# CAN.net
KiCad netlist of a schematic drawn in Altium Designer
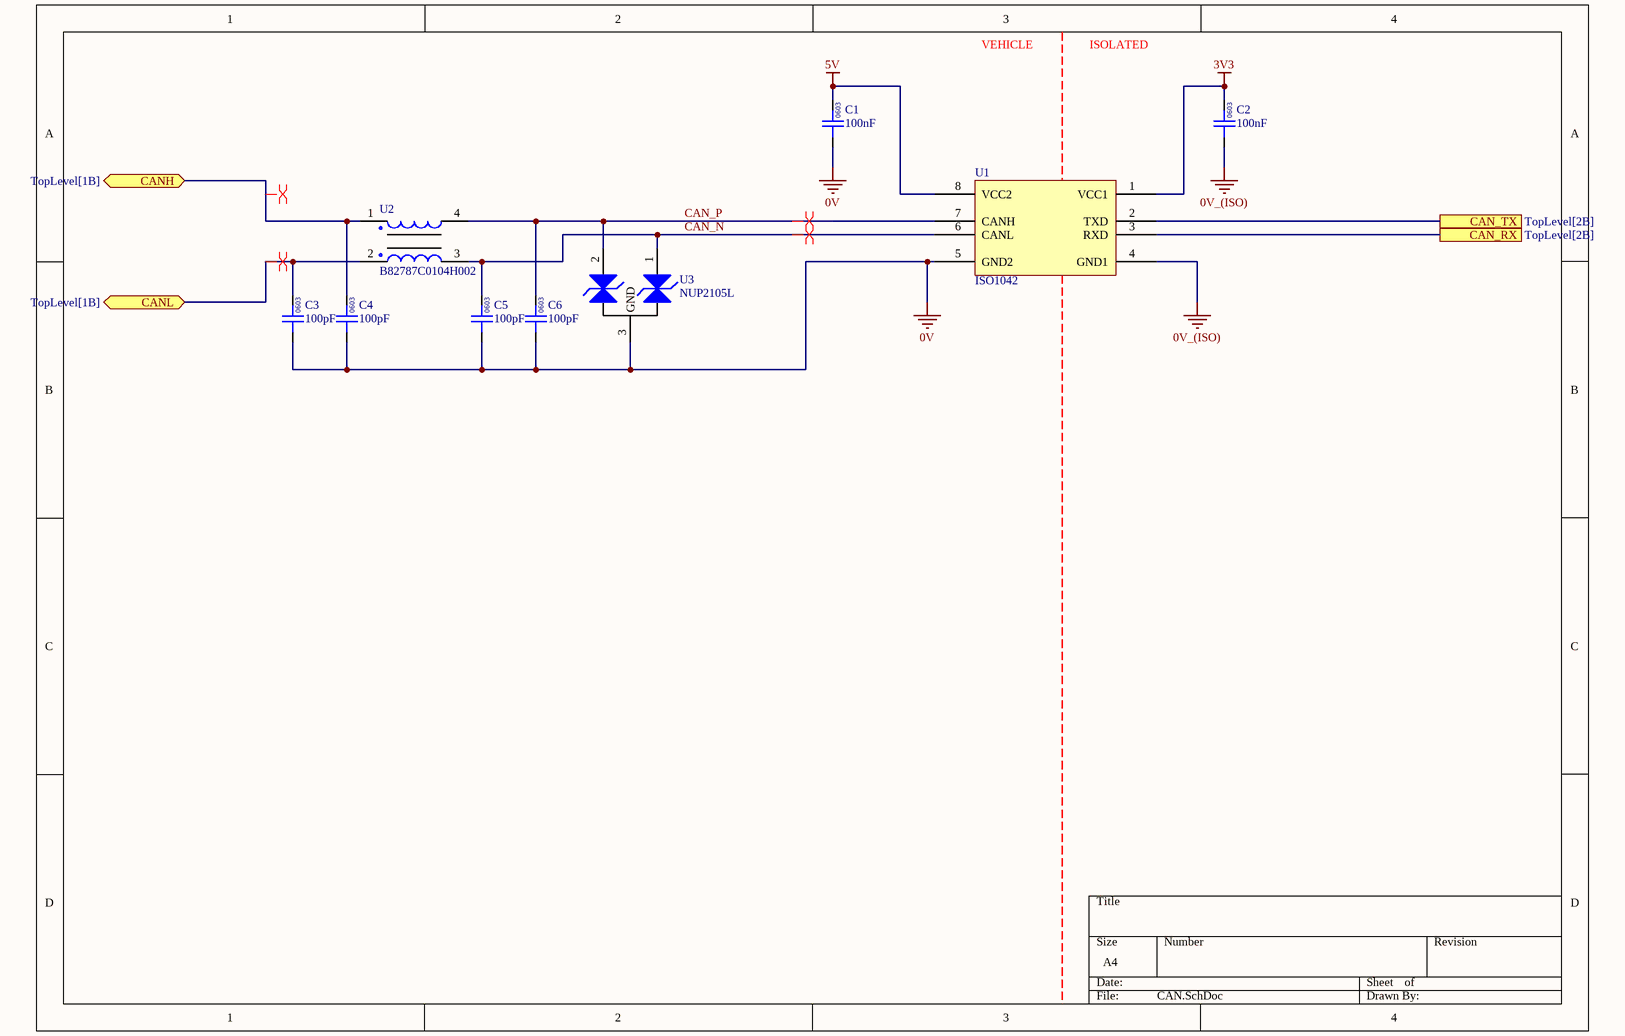
[diagram p0: CAN.SchDoc]

(export (version "E")
  (design (tool "Eeschema 10.0.6"))
  (components
    (comp (ref "C1")
      (value "100nF")
      (footprint "0603")
      (fields
        (field (name "PART NUMBER") "GCM188L81H104KA57D")
        (field (name "MANUFACTURER") "muRata")
        (field (name "TOLERANCE") "±10%")
      )
      (libsource (lib "ts_standard_library") (part "Capacitor 0603"))
    )
    (comp (ref "C2")
      (value "100nF")
      (footprint "0603")
      (fields
        (field (name "PART NUMBER") "GCM188L81H104KA57D")
        (field (name "MANUFACTURER") "muRata")
        (field (name "TOLERANCE") "±10%")
      )
      (libsource (lib "ts_standard_library") (part "Capacitor 0603"))
    )
    (comp (ref "C3")
      (value "100pF")
      (footprint "0603")
      (fields
        (field (name "PART NUMBER") "GRM1885C1H101JA01D")
        (field (name "MANUFACTURER") "Murata Electronics")
        (field (name "TOLERANCE") "±5%")
      )
      (libsource (lib "ts_standard_library") (part "Capacitor 0603"))
    )
    (comp (ref "C4")
      (value "100pF")
      (footprint "0603")
      (fields
        (field (name "PART NUMBER") "GRM1885C1H101JA01D")
        (field (name "MANUFACTURER") "Murata Electronics")
        (field (name "TOLERANCE") "±5%")
      )
      (libsource (lib "ts_standard_library") (part "Capacitor 0603"))
    )
    (comp (ref "C5")
      (value "100pF")
      (footprint "0603")
      (fields
        (field (name "PART NUMBER") "GRM1885C1H101JA01D")
        (field (name "MANUFACTURER") "Murata Electronics")
        (field (name "TOLERANCE") "±5%")
      )
      (libsource (lib "ts_standard_library") (part "Capacitor 0603"))
    )
    (comp (ref "C6")
      (value "100pF")
      (footprint "0603")
      (fields
        (field (name "PART NUMBER") "GRM1885C1H101JA01D")
        (field (name "MANUFACTURER") "Murata Electronics")
        (field (name "TOLERANCE") "±5%")
      )
      (libsource (lib "ts_standard_library") (part "Capacitor 0603"))
    )
    (comp (ref "U1")
      (value "ISO1042")
      (footprint "TI-SOIC-8")
      (description "IC CAN TRANSCEIVER 1/1 8SOIC")
      (fields
        (field (name "MANUFACTURER") "Texas Instruments")
        (field (name "DIGIKEY PART NUMBER") "296-ISO1042BQDWVQ1-ND")
      )
      (libsource (lib "ts_standard_library") (part "ISO1042"))
    )
    (comp (ref "U2")
      (value "B82787C0104H002")
      (footprint "TDK 4-PC Pad")
      (fields
        (field (name "MANUFACTURER") "EPCOS (TDK)")
        (field (name "DIGIKEY PART NUMBER") "495-4598-1-ND")
      )
      (libsource (lib "ts_standard_library") (part "B82787C0104H002"))
    )
    (comp (ref "U3")
      (value "NUP2105L")
      (footprint "ON SOT-23")
      (description "Dual Line CAN Bus Protector")
      (fields
        (field (name "MANUFACTURER") "ON Semiconductor")
        (field (name "DIGIKEY PART NUMBER") "NUP2105LT1GOSCT-ND")
      )
      (libsource (lib "ts_standard_library") (part "NUP2105L"))
    )
  )
  (nets
    (net (code "1") (name "/CANH") (class "Default")
      (node (ref "C4") (pin "2") (pinfunction "2_2") (pintype "passive"))
      (node (ref "U2") (pin "1") (pinfunction "1_1") (pintype "passive"))
    )
    (net (code "2") (name "/CANL") (class "Default")
      (node (ref "C3") (pin "2") (pinfunction "2_2") (pintype "passive"))
      (node (ref "U2") (pin "2") (pinfunction "2_2") (pintype "passive"))
    )
    (net (code "3") (name "/CAN_N") (class "Default")
      (node (ref "C5") (pin "2") (pinfunction "2_2") (pintype "passive"))
      (node (ref "U1") (pin "6") (pinfunction "CANL_6") (pintype "passive"))
      (node (ref "U2") (pin "3") (pinfunction "3_3") (pintype "passive"))
      (node (ref "U3") (pin "1") (pinfunction "CAN_H_1") (pintype "passive"))
    )
    (net (code "4") (name "/CAN_P") (class "Default")
      (node (ref "C6") (pin "2") (pinfunction "2_2") (pintype "passive"))
      (node (ref "U1") (pin "7") (pinfunction "CANH_7") (pintype "passive"))
      (node (ref "U2") (pin "4") (pinfunction "4_4") (pintype "passive"))
      (node (ref "U3") (pin "2") (pinfunction "CAN_L_2") (pintype "passive"))
    )
    (net (code "5") (name "/CAN_RX") (class "Default")
      (node (ref "U1") (pin "3") (pinfunction "RXD_3") (pintype "passive"))
    )
    (net (code "6") (name "/CAN_TX") (class "Default")
      (node (ref "U1") (pin "2") (pinfunction "TXD_2") (pintype "passive"))
    )
    (net (code "7") (name "0V") (class "Default")
      (node (ref "C1") (pin "1") (pinfunction "1_1") (pintype "passive"))
      (node (ref "C3") (pin "1") (pinfunction "1_1") (pintype "passive"))
      (node (ref "C4") (pin "1") (pinfunction "1_1") (pintype "passive"))
      (node (ref "C5") (pin "1") (pinfunction "1_1") (pintype "passive"))
      (node (ref "C6") (pin "1") (pinfunction "1_1") (pintype "passive"))
      (node (ref "U1") (pin "5") (pinfunction "GND2_5") (pintype "passive"))
      (node (ref "U3") (pin "3") (pinfunction "GND_3") (pintype "passive"))
    )
    (net (code "8") (name "0V_(ISO)") (class "Default")
      (node (ref "C2") (pin "1") (pinfunction "1_1") (pintype "passive"))
      (node (ref "U1") (pin "4") (pinfunction "GND1_4") (pintype "passive"))
    )
    (net (code "9") (name "3V3") (class "Default")
      (node (ref "C2") (pin "2") (pinfunction "2_2") (pintype "passive"))
      (node (ref "U1") (pin "1") (pinfunction "VCC1_1") (pintype "passive"))
    )
    (net (code "10") (name "5V") (class "Default")
      (node (ref "C1") (pin "2") (pinfunction "2_2") (pintype "passive"))
      (node (ref "U1") (pin "8") (pinfunction "VCC2_8") (pintype "passive"))
    )
  )
)
